# KR55_soundgen.net
KiCad netlist of a schematic drawn in EAGLE
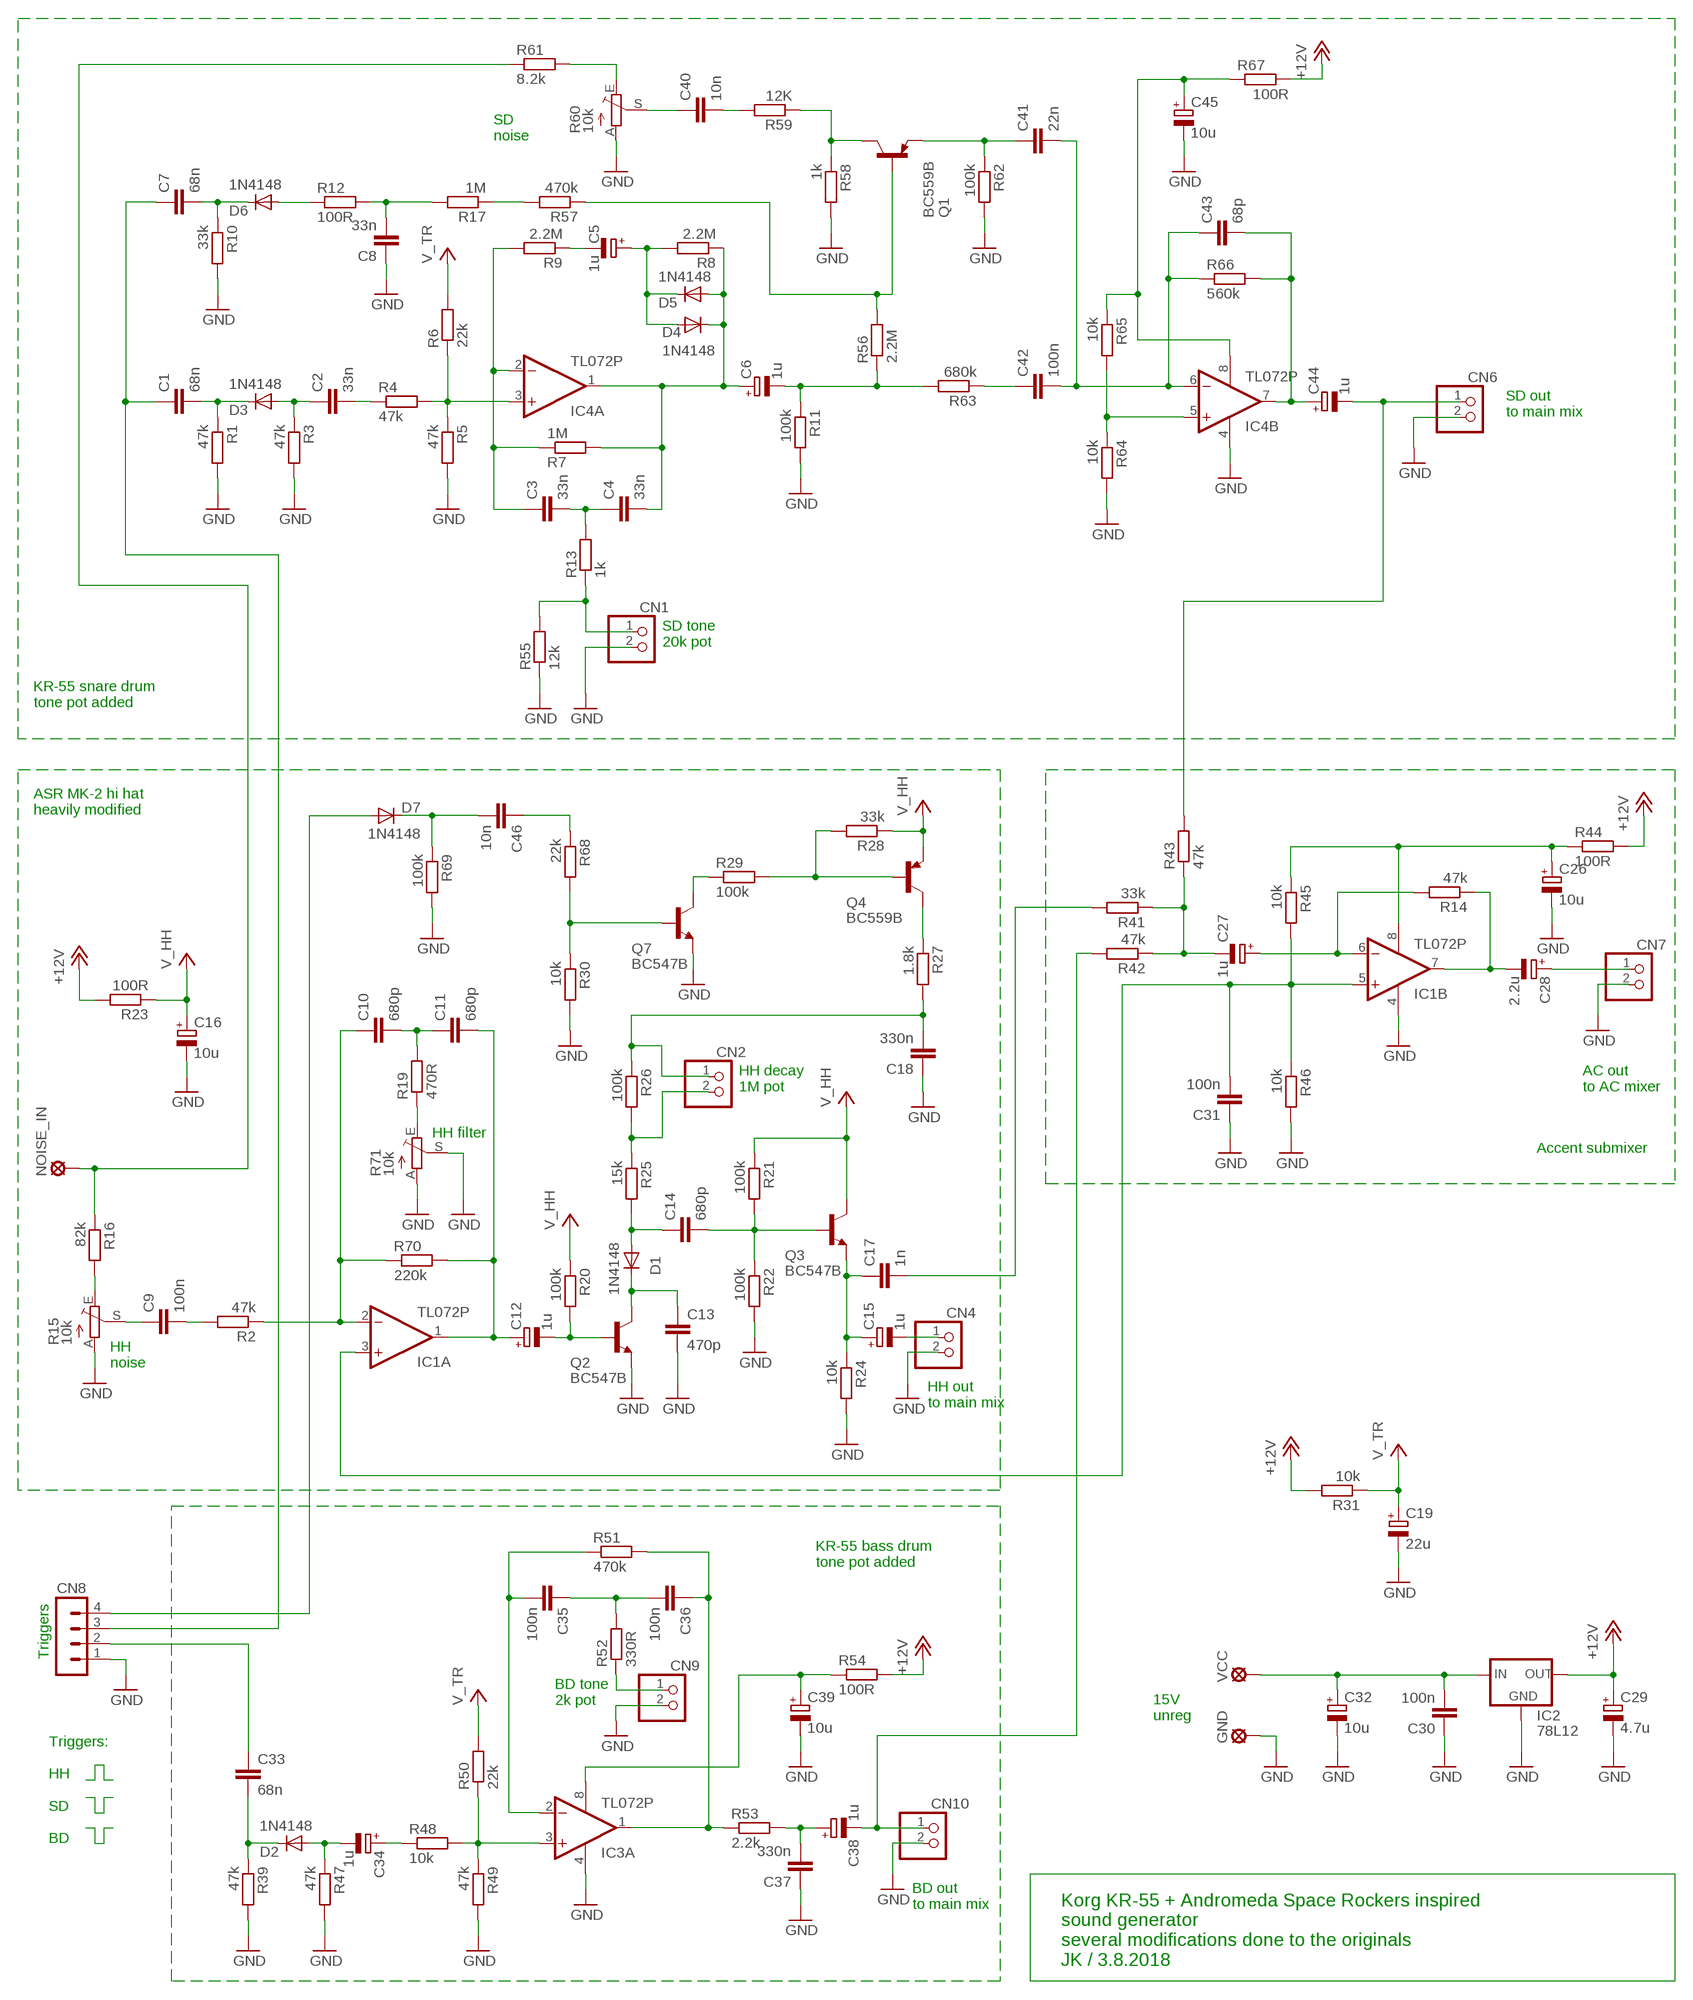
[diagram p0: schematic, sheet 1]

(export (version "E")
  (design (tool "Eeschema 10.0.6"))
  (components
    (comp (ref "C1")
      (value "68n")
      (footprint "eagle-import:C0805")
      (libsource (lib "eagle-import") (part "C-EUC0805"))
    )
    (comp (ref "C2")
      (value "33n")
      (footprint "eagle-import:C0805")
      (libsource (lib "eagle-import") (part "C-EUC0805"))
    )
    (comp (ref "C3")
      (value "33n")
      (footprint "eagle-import:C0805")
      (libsource (lib "eagle-import") (part "C-EUC0805"))
    )
    (comp (ref "C4")
      (value "33n")
      (footprint "eagle-import:C0805")
      (libsource (lib "eagle-import") (part "C-EUC0805"))
    )
    (comp (ref "C5")
      (value "1u")
      (footprint "eagle-import:SMC_A")
      (libsource (lib "eagle-import") (part "CPOL-EUSMCA"))
    )
    (comp (ref "C6")
      (value "1u")
      (footprint "eagle-import:SMC_A")
      (libsource (lib "eagle-import") (part "CPOL-EUSMCA"))
    )
    (comp (ref "C7")
      (value "68n")
      (footprint "eagle-import:C0805")
      (libsource (lib "eagle-import") (part "C-EUC0805"))
    )
    (comp (ref "C8")
      (value "33n")
      (footprint "eagle-import:C0805")
      (libsource (lib "eagle-import") (part "C-EUC0805"))
    )
    (comp (ref "C9")
      (value "100n")
      (footprint "eagle-import:C0805")
      (libsource (lib "eagle-import") (part "C-EUC0805"))
    )
    (comp (ref "C10")
      (value "680p")
      (footprint "eagle-import:C0805")
      (libsource (lib "eagle-import") (part "C-EUC0805"))
    )
    (comp (ref "C11")
      (value "680p")
      (footprint "eagle-import:C0805")
      (libsource (lib "eagle-import") (part "C-EUC0805"))
    )
    (comp (ref "C12")
      (value "1u")
      (footprint "eagle-import:SMC_A")
      (libsource (lib "eagle-import") (part "CPOL-EUSMCA"))
    )
    (comp (ref "C13")
      (value "470p")
      (footprint "eagle-import:C0805")
      (libsource (lib "eagle-import") (part "C-EUC0805"))
    )
    (comp (ref "C14")
      (value "680p")
      (footprint "eagle-import:C0805")
      (libsource (lib "eagle-import") (part "C-EUC0805"))
    )
    (comp (ref "C15")
      (value "1u")
      (footprint "eagle-import:SMC_A")
      (libsource (lib "eagle-import") (part "CPOL-EUSMCA"))
    )
    (comp (ref "C16")
      (value "10u")
      (footprint "eagle-import:E2,5-5")
      (libsource (lib "eagle-import") (part "CPOL-EUE2.5-5"))
    )
    (comp (ref "C17")
      (value "1n")
      (footprint "eagle-import:C0805")
      (libsource (lib "eagle-import") (part "C-EUC0805"))
    )
    (comp (ref "C18")
      (value "330n")
      (footprint "eagle-import:C0805")
      (libsource (lib "eagle-import") (part "C-EUC0805"))
    )
    (comp (ref "C19")
      (value "22u")
      (footprint "eagle-import:E2,5-5")
      (libsource (lib "eagle-import") (part "CPOL-EUE2.5-5"))
    )
    (comp (ref "C26")
      (value "10u")
      (footprint "eagle-import:E5-5")
      (libsource (lib "eagle-import") (part "CPOL-EUE5-5"))
    )
    (comp (ref "C27")
      (value "1u")
      (footprint "eagle-import:SMC_A")
      (libsource (lib "eagle-import") (part "CPOL-EUSMCA"))
    )
    (comp (ref "C28")
      (value "2.2u")
      (footprint "eagle-import:SMC_A")
      (libsource (lib "eagle-import") (part "CPOL-EUSMCA"))
    )
    (comp (ref "C29")
      (value "4.7u")
      (footprint "eagle-import:SMC_A")
      (libsource (lib "eagle-import") (part "CPOL-EUSMCA"))
    )
    (comp (ref "C30")
      (value "100n")
      (footprint "eagle-import:C0805")
      (libsource (lib "eagle-import") (part "C-EUC0805"))
    )
    (comp (ref "C31")
      (value "100n")
      (footprint "eagle-import:C0805")
      (libsource (lib "eagle-import") (part "C-EUC0805"))
    )
    (comp (ref "C32")
      (value "10u")
      (footprint "eagle-import:E2,5-5")
      (libsource (lib "eagle-import") (part "CPOL-EUE2.5-5"))
    )
    (comp (ref "C33")
      (value "68n")
      (footprint "eagle-import:C0805")
      (libsource (lib "eagle-import") (part "C-EUC0805"))
    )
    (comp (ref "C34")
      (value "1u")
      (footprint "eagle-import:SMC_A")
      (libsource (lib "eagle-import") (part "CPOL-EUSMCA"))
    )
    (comp (ref "C35")
      (value "100n")
      (footprint "eagle-import:C0805")
      (libsource (lib "eagle-import") (part "C-EUC0805"))
    )
    (comp (ref "C36")
      (value "100n")
      (footprint "eagle-import:C0805")
      (libsource (lib "eagle-import") (part "C-EUC0805"))
    )
    (comp (ref "C37")
      (value "330n")
      (footprint "eagle-import:C0805")
      (libsource (lib "eagle-import") (part "C-EUC0805"))
    )
    (comp (ref "C38")
      (value "1u")
      (footprint "eagle-import:SMC_A")
      (libsource (lib "eagle-import") (part "CPOL-EUSMCA"))
    )
    (comp (ref "C39")
      (value "10u")
      (footprint "eagle-import:E2,5-5")
      (libsource (lib "eagle-import") (part "CPOL-EUE2.5-5"))
    )
    (comp (ref "C40")
      (value "10n")
      (footprint "eagle-import:C1206")
      (libsource (lib "eagle-import") (part "C-EUC1206"))
    )
    (comp (ref "C41")
      (value "22n")
      (footprint "eagle-import:C0805")
      (libsource (lib "eagle-import") (part "C-EUC0805"))
    )
    (comp (ref "C42")
      (value "100n")
      (footprint "eagle-import:C050-024X044")
      (libsource (lib "eagle-import") (part "C-EU050-024X044"))
    )
    (comp (ref "C43")
      (value "68p")
      (footprint "eagle-import:C0805")
      (libsource (lib "eagle-import") (part "C-EUC0805"))
    )
    (comp (ref "C44")
      (value "1u")
      (footprint "eagle-import:SMC_A")
      (libsource (lib "eagle-import") (part "CPOL-EUSMCA"))
    )
    (comp (ref "C45")
      (value "10u")
      (footprint "eagle-import:E2,5-5")
      (libsource (lib "eagle-import") (part "CPOL-EUE2.5-5"))
    )
    (comp (ref "C46")
      (value "10n")
      (footprint "eagle-import:C0805")
      (libsource (lib "eagle-import") (part "C-EUC0805"))
    )
    (comp (ref "CN1")
      (value "PINHD-1X2")
      (footprint "eagle-import:1X02")
      (libsource (lib "eagle-import") (part "PINHD-1X2"))
    )
    (comp (ref "CN2")
      (value "PINHD-1X2")
      (footprint "eagle-import:1X02")
      (libsource (lib "eagle-import") (part "PINHD-1X2"))
    )
    (comp (ref "CN4")
      (value "PINHD-1X2")
      (footprint "eagle-import:1X02")
      (libsource (lib "eagle-import") (part "PINHD-1X2"))
    )
    (comp (ref "CN6")
      (value "PINHD-1X2")
      (footprint "eagle-import:1X02")
      (libsource (lib "eagle-import") (part "PINHD-1X2"))
    )
    (comp (ref "CN7")
      (value "PINHD-1X2")
      (footprint "eagle-import:1X02")
      (libsource (lib "eagle-import") (part "PINHD-1X2"))
    )
    (comp (ref "CN8")
      (value "MA04-1")
      (footprint "eagle-import:MA04-1")
      (libsource (lib "eagle-import") (part "MA04-1"))
    )
    (comp (ref "CN9")
      (value "PINHD-1X2")
      (footprint "eagle-import:1X02")
      (libsource (lib "eagle-import") (part "PINHD-1X2"))
    )
    (comp (ref "CN10")
      (value "PINHD-1X2")
      (footprint "eagle-import:1X02")
      (libsource (lib "eagle-import") (part "PINHD-1X2"))
    )
    (comp (ref "D1")
      (value "1N4148")
      (footprint "eagle-import:SOD80C")
      (libsource (lib "eagle-import") (part "DIODE-SOD80C"))
    )
    (comp (ref "D2")
      (value "1N4148")
      (footprint "eagle-import:SOD80C")
      (libsource (lib "eagle-import") (part "DIODE-SOD80C"))
    )
    (comp (ref "D3")
      (value "1N4148")
      (footprint "eagle-import:SOD80C")
      (libsource (lib "eagle-import") (part "DIODE-SOD80C"))
    )
    (comp (ref "D4")
      (value "1N4148")
      (footprint "eagle-import:SOD80C")
      (libsource (lib "eagle-import") (part "DIODE-SOD80C"))
    )
    (comp (ref "D5")
      (value "1N4148")
      (footprint "eagle-import:SOD80C")
      (libsource (lib "eagle-import") (part "DIODE-SOD80C"))
    )
    (comp (ref "D6")
      (value "1N4148")
      (footprint "eagle-import:SOD80C")
      (libsource (lib "eagle-import") (part "DIODE-SOD80C"))
    )
    (comp (ref "D7")
      (value "1N4148")
      (footprint "eagle-import:DO35-10")
      (libsource (lib "eagle-import") (part "DIODE-DO35-10"))
    )
    (comp (ref "GND")
      (value "LSP10")
      (footprint "eagle-import:LSP10")
      (libsource (lib "eagle-import") (part "LSP10"))
    )
    (comp (ref "IC1")
      (value "TL072P")
      (footprint "eagle-import:DIL08")
      (libsource (lib "eagle-import") (part "TL072P"))
    )
    (comp (ref "IC2")
      (value "78L12")
      (footprint "eagle-import:78LXX")
      (libsource (lib "eagle-import") (part "78LXX"))
    )
    (comp (ref "IC3")
      (value "TL072P")
      (footprint "eagle-import:DIL08")
      (libsource (lib "eagle-import") (part "TL072P"))
    )
    (comp (ref "IC4")
      (value "TL072P")
      (footprint "eagle-import:DIL08")
      (libsource (lib "eagle-import") (part "TL072P"))
    )
    (comp (ref "NOISE_IN")
      (value "LSP10")
      (footprint "eagle-import:LSP10")
      (libsource (lib "eagle-import") (part "LSP10"))
    )
    (comp (ref "Q1")
      (value "BC559B")
      (footprint "eagle-import:TO92-EBC")
      (libsource (lib "eagle-import") (part "BC559B"))
    )
    (comp (ref "Q2")
      (value "BC547B")
      (footprint "eagle-import:TO92")
      (libsource (lib "eagle-import") (part "BC547B"))
    )
    (comp (ref "Q3")
      (value "BC547B")
      (footprint "eagle-import:TO92")
      (libsource (lib "eagle-import") (part "BC547B"))
    )
    (comp (ref "Q4")
      (value "BC559B")
      (footprint "eagle-import:TO92-EBC")
      (libsource (lib "eagle-import") (part "BC559B"))
    )
    (comp (ref "Q7")
      (value "BC547B")
      (footprint "eagle-import:TO92")
      (libsource (lib "eagle-import") (part "BC547B"))
    )
    (comp (ref "R1")
      (value "47k")
      (footprint "eagle-import:R0805")
      (libsource (lib "eagle-import") (part "R-EU_R0805"))
    )
    (comp (ref "R2")
      (value "47k")
      (footprint "eagle-import:R0805")
      (libsource (lib "eagle-import") (part "R-EU_R0805"))
    )
    (comp (ref "R3")
      (value "47k")
      (footprint "eagle-import:R0805")
      (libsource (lib "eagle-import") (part "R-EU_R0805"))
    )
    (comp (ref "R4")
      (value "47k")
      (footprint "eagle-import:R0805")
      (libsource (lib "eagle-import") (part "R-EU_R0805"))
    )
    (comp (ref "R5")
      (value "47k")
      (footprint "eagle-import:R0805")
      (libsource (lib "eagle-import") (part "R-EU_R0805"))
    )
    (comp (ref "R6")
      (value "22k")
      (footprint "eagle-import:R0805")
      (libsource (lib "eagle-import") (part "R-EU_R0805"))
    )
    (comp (ref "R7")
      (value "1M")
      (footprint "eagle-import:R0805")
      (libsource (lib "eagle-import") (part "R-EU_R0805"))
    )
    (comp (ref "R8")
      (value "2.2M")
      (footprint "eagle-import:R0805")
      (libsource (lib "eagle-import") (part "R-EU_R0805"))
    )
    (comp (ref "R9")
      (value "2.2M")
      (footprint "eagle-import:R0805")
      (libsource (lib "eagle-import") (part "R-EU_R0805"))
    )
    (comp (ref "R10")
      (value "33k")
      (footprint "eagle-import:R0805")
      (libsource (lib "eagle-import") (part "R-EU_R0805"))
    )
    (comp (ref "R11")
      (value "100k")
      (footprint "eagle-import:R0805")
      (libsource (lib "eagle-import") (part "R-EU_R0805"))
    )
    (comp (ref "R12")
      (value "100R")
      (footprint "eagle-import:R0805")
      (libsource (lib "eagle-import") (part "R-EU_R0805"))
    )
    (comp (ref "R13")
      (value "1k")
      (footprint "eagle-import:R0805")
      (libsource (lib "eagle-import") (part "R-EU_R0805"))
    )
    (comp (ref "R14")
      (value "47k")
      (footprint "eagle-import:R0805")
      (libsource (lib "eagle-import") (part "R-EU_R0805"))
    )
    (comp (ref "R15")
      (value "10k")
      (footprint "eagle-import:S63X")
      (libsource (lib "eagle-import") (part "TRIM_EU-S63X"))
    )
    (comp (ref "R16")
      (value "82k")
      (footprint "eagle-import:R0805")
      (libsource (lib "eagle-import") (part "R-EU_R0805"))
    )
    (comp (ref "R17")
      (value "1M")
      (footprint "eagle-import:R0805")
      (libsource (lib "eagle-import") (part "R-EU_R0805"))
    )
    (comp (ref "R19")
      (value "470R")
      (footprint "eagle-import:0207_10")
      (libsource (lib "eagle-import") (part "R-EU_0207/10"))
    )
    (comp (ref "R20")
      (value "100k")
      (footprint "eagle-import:0207_10")
      (libsource (lib "eagle-import") (part "R-EU_0207/10"))
    )
    (comp (ref "R21")
      (value "100k")
      (footprint "eagle-import:R0805")
      (libsource (lib "eagle-import") (part "R-EU_R0805"))
    )
    (comp (ref "R22")
      (value "100k")
      (footprint "eagle-import:R0805")
      (libsource (lib "eagle-import") (part "R-EU_R0805"))
    )
    (comp (ref "R23")
      (value "100R")
      (footprint "eagle-import:R0805")
      (libsource (lib "eagle-import") (part "R-EU_R0805"))
    )
    (comp (ref "R24")
      (value "10k")
      (footprint "eagle-import:R0805")
      (libsource (lib "eagle-import") (part "R-EU_R0805"))
    )
    (comp (ref "R25")
      (value "15k")
      (footprint "eagle-import:0207_10")
      (libsource (lib "eagle-import") (part "R-EU_0207/10"))
    )
    (comp (ref "R26")
      (value "100k")
      (footprint "eagle-import:R0805")
      (libsource (lib "eagle-import") (part "R-EU_R0805"))
    )
    (comp (ref "R27")
      (value "1.8k")
      (footprint "eagle-import:0207_10")
      (libsource (lib "eagle-import") (part "R-EU_0207/10"))
    )
    (comp (ref "R28")
      (value "33k")
      (footprint "eagle-import:R0805")
      (libsource (lib "eagle-import") (part "R-EU_R0805"))
    )
    (comp (ref "R29")
      (value "100k")
      (footprint "eagle-import:R0805")
      (libsource (lib "eagle-import") (part "R-EU_R0805"))
    )
    (comp (ref "R30")
      (value "10k")
      (footprint "eagle-import:R0805")
      (libsource (lib "eagle-import") (part "R-EU_R0805"))
    )
    (comp (ref "R31")
      (value "10k")
      (footprint "eagle-import:R0805")
      (libsource (lib "eagle-import") (part "R-EU_R0805"))
    )
    (comp (ref "R39")
      (value "47k")
      (footprint "eagle-import:R0805")
      (libsource (lib "eagle-import") (part "R-EU_R0805"))
    )
    (comp (ref "R41")
      (value "33k")
      (footprint "eagle-import:R0805")
      (libsource (lib "eagle-import") (part "R-EU_R0805"))
    )
    (comp (ref "R42")
      (value "47k")
      (footprint "eagle-import:R0805")
      (libsource (lib "eagle-import") (part "R-EU_R0805"))
    )
    (comp (ref "R43")
      (value "47k")
      (footprint "eagle-import:R0805")
      (libsource (lib "eagle-import") (part "R-EU_R0805"))
    )
    (comp (ref "R44")
      (value "100R")
      (footprint "eagle-import:0207_10")
      (libsource (lib "eagle-import") (part "R-EU_0207/10"))
    )
    (comp (ref "R45")
      (value "10k")
      (footprint "eagle-import:R0805")
      (libsource (lib "eagle-import") (part "R-EU_R0805"))
    )
    (comp (ref "R46")
      (value "10k")
      (footprint "eagle-import:R0805")
      (libsource (lib "eagle-import") (part "R-EU_R0805"))
    )
    (comp (ref "R47")
      (value "47k")
      (footprint "eagle-import:R0805")
      (libsource (lib "eagle-import") (part "R-EU_R0805"))
    )
    (comp (ref "R48")
      (value "10k")
      (footprint "eagle-import:R0805")
      (libsource (lib "eagle-import") (part "R-EU_R0805"))
    )
    (comp (ref "R49")
      (value "47k")
      (footprint "eagle-import:R0805")
      (libsource (lib "eagle-import") (part "R-EU_R0805"))
    )
    (comp (ref "R50")
      (value "22k")
      (footprint "eagle-import:R0805")
      (libsource (lib "eagle-import") (part "R-EU_R0805"))
    )
    (comp (ref "R51")
      (value "470k")
      (footprint "eagle-import:R0805")
      (libsource (lib "eagle-import") (part "R-EU_R0805"))
    )
    (comp (ref "R52")
      (value "330R")
      (footprint "eagle-import:R0805")
      (libsource (lib "eagle-import") (part "R-EU_R0805"))
    )
    (comp (ref "R53")
      (value "2.2k")
      (footprint "eagle-import:0207_10")
      (libsource (lib "eagle-import") (part "R-EU_0207/10"))
    )
    (comp (ref "R54")
      (value "100R")
      (footprint "eagle-import:0207_10")
      (libsource (lib "eagle-import") (part "R-EU_0207/10"))
    )
    (comp (ref "R55")
      (value "12k")
      (footprint "eagle-import:R0805")
      (libsource (lib "eagle-import") (part "R-EU_R0805"))
    )
    (comp (ref "R56")
      (value "2.2M")
      (footprint "eagle-import:R0805")
      (libsource (lib "eagle-import") (part "R-EU_R0805"))
    )
    (comp (ref "R57")
      (value "470k")
      (footprint "eagle-import:R0805")
      (libsource (lib "eagle-import") (part "R-EU_R0805"))
    )
    (comp (ref "R58")
      (value "1k")
      (footprint "eagle-import:R0805")
      (libsource (lib "eagle-import") (part "R-EU_R0805"))
    )
    (comp (ref "R59")
      (value "12K")
      (footprint "eagle-import:R0805")
      (libsource (lib "eagle-import") (part "R-EU_R0805"))
    )
    (comp (ref "R60")
      (value "10k")
      (footprint "eagle-import:S63X")
      (libsource (lib "eagle-import") (part "TRIM_EU-S63X"))
    )
    (comp (ref "R61")
      (value "8.2k")
      (footprint "eagle-import:R0805")
      (libsource (lib "eagle-import") (part "R-EU_R0805"))
    )
    (comp (ref "R62")
      (value "100k")
      (footprint "eagle-import:R0805")
      (libsource (lib "eagle-import") (part "R-EU_R0805"))
    )
    (comp (ref "R63")
      (value "680k")
      (footprint "eagle-import:R0805")
      (libsource (lib "eagle-import") (part "R-EU_R0805"))
    )
    (comp (ref "R64")
      (value "10k")
      (footprint "eagle-import:R0805")
      (libsource (lib "eagle-import") (part "R-EU_R0805"))
    )
    (comp (ref "R65")
      (value "10k")
      (footprint "eagle-import:R0805")
      (libsource (lib "eagle-import") (part "R-EU_R0805"))
    )
    (comp (ref "R66")
      (value "560k")
      (footprint "eagle-import:R0805")
      (libsource (lib "eagle-import") (part "R-EU_R0805"))
    )
    (comp (ref "R67")
      (value "100R")
      (footprint "eagle-import:R0805")
      (libsource (lib "eagle-import") (part "R-EU_R0805"))
    )
    (comp (ref "R68")
      (value "22k")
      (footprint "eagle-import:R0805")
      (libsource (lib "eagle-import") (part "R-EU_R0805"))
    )
    (comp (ref "R69")
      (value "100k")
      (footprint "eagle-import:R0805")
      (libsource (lib "eagle-import") (part "R-EU_R0805"))
    )
    (comp (ref "R70")
      (value "220k")
      (footprint "eagle-import:R0805")
      (libsource (lib "eagle-import") (part "R-EU_R0805"))
    )
    (comp (ref "R71")
      (value "10k")
      (footprint "eagle-import:S63X")
      (libsource (lib "eagle-import") (part "TRIM_EU-S63X"))
    )
    (comp (ref "VCC")
      (value "LSP10")
      (footprint "eagle-import:LSP10")
      (libsource (lib "eagle-import") (part "LSP10"))
    )
  )
  (nets
    (net (code "1") (name "+12V") (class "Default")
      (node (ref "C29") (pin "+") (pinfunction "+_+") (pintype "passive"))
      (node (ref "IC2") (pin "OUT") (pinfunction "OUT_OUT") (pintype "passive"))
      (node (ref "R23") (pin "2") (pinfunction "2_2") (pintype "passive"))
      (node (ref "R31") (pin "2") (pinfunction "2_2") (pintype "passive"))
      (node (ref "R44") (pin "2") (pinfunction "2_2") (pintype "passive"))
      (node (ref "R54") (pin "2") (pinfunction "2_2") (pintype "passive"))
      (node (ref "R67") (pin "2") (pinfunction "2_2") (pintype "passive"))
    )
    (net (code "2") (name "GND") (class "Default")
      (node (ref "C13") (pin "2") (pinfunction "2_2") (pintype "passive"))
      (node (ref "C16") (pin "-") (pinfunction "-_-") (pintype "passive"))
      (node (ref "C18") (pin "1") (pinfunction "1_1") (pintype "passive"))
      (node (ref "C19") (pin "-") (pinfunction "-_-") (pintype "passive"))
      (node (ref "C26") (pin "-") (pinfunction "-_-") (pintype "passive"))
      (node (ref "C29") (pin "-") (pinfunction "-_-") (pintype "passive"))
      (node (ref "C30") (pin "1") (pinfunction "1_1") (pintype "passive"))
      (node (ref "C31") (pin "1") (pinfunction "1_1") (pintype "passive"))
      (node (ref "C32") (pin "-") (pinfunction "-_-") (pintype "passive"))
      (node (ref "C37") (pin "1") (pinfunction "1_1") (pintype "passive"))
      (node (ref "C39") (pin "-") (pinfunction "-_-") (pintype "passive"))
      (node (ref "C45") (pin "-") (pinfunction "-_-") (pintype "passive"))
      (node (ref "C8") (pin "1") (pinfunction "1_1") (pintype "passive"))
      (node (ref "CN1") (pin "2") (pinfunction "2_2") (pintype "passive"))
      (node (ref "CN10") (pin "2") (pinfunction "2_2") (pintype "passive"))
      (node (ref "CN4") (pin "2") (pinfunction "2_2") (pintype "passive"))
      (node (ref "CN6") (pin "2") (pinfunction "2_2") (pintype "passive"))
      (node (ref "CN7") (pin "2") (pinfunction "2_2") (pintype "passive"))
      (node (ref "CN8") (pin "1") (pinfunction "1_1") (pintype "passive"))
      (node (ref "CN9") (pin "2") (pinfunction "2_2") (pintype "passive"))
      (node (ref "GND") (pin "MP") (pinfunction "MP_MP") (pintype "passive"))
      (node (ref "IC1") (pin "4") (pinfunction "V-_4") (pintype "power_in"))
      (node (ref "IC2") (pin "GND") (pinfunction "GND_GND") (pintype "input"))
      (node (ref "IC3") (pin "4") (pinfunction "V-_4") (pintype "power_in"))
      (node (ref "IC4") (pin "4") (pinfunction "V-_4") (pintype "power_in"))
      (node (ref "Q2") (pin "1") (pinfunction "E_1") (pintype "passive"))
      (node (ref "Q7") (pin "1") (pinfunction "E_1") (pintype "passive"))
      (node (ref "R1") (pin "2") (pinfunction "2_2") (pintype "passive"))
      (node (ref "R10") (pin "2") (pinfunction "2_2") (pintype "passive"))
      (node (ref "R11") (pin "2") (pinfunction "2_2") (pintype "passive"))
      (node (ref "R15") (pin "A") (pinfunction "A_A") (pintype "passive"))
      (node (ref "R22") (pin "2") (pinfunction "2_2") (pintype "passive"))
      (node (ref "R24") (pin "2") (pinfunction "2_2") (pintype "passive"))
      (node (ref "R3") (pin "2") (pinfunction "2_2") (pintype "passive"))
      (node (ref "R30") (pin "2") (pinfunction "2_2") (pintype "passive"))
      (node (ref "R39") (pin "2") (pinfunction "2_2") (pintype "passive"))
      (node (ref "R46") (pin "2") (pinfunction "2_2") (pintype "passive"))
      (node (ref "R47") (pin "2") (pinfunction "2_2") (pintype "passive"))
      (node (ref "R49") (pin "2") (pinfunction "2_2") (pintype "passive"))
      (node (ref "R5") (pin "2") (pinfunction "2_2") (pintype "passive"))
      (node (ref "R55") (pin "1") (pinfunction "1_1") (pintype "passive"))
      (node (ref "R58") (pin "2") (pinfunction "2_2") (pintype "passive"))
      (node (ref "R60") (pin "A") (pinfunction "A_A") (pintype "passive"))
      (node (ref "R62") (pin "2") (pinfunction "2_2") (pintype "passive"))
      (node (ref "R64") (pin "2") (pinfunction "2_2") (pintype "passive"))
      (node (ref "R69") (pin "2") (pinfunction "2_2") (pintype "passive"))
      (node (ref "R71") (pin "A") (pinfunction "A_A") (pintype "passive"))
      (node (ref "R71") (pin "S") (pinfunction "S_S") (pintype "passive"))
    )
    (net (code "3") (name "Net-(C1-Pad1)") (class "Default")
      (node (ref "C1") (pin "1") (pinfunction "1_1") (pintype "passive"))
      (node (ref "C7") (pin "1") (pinfunction "1_1") (pintype "passive"))
      (node (ref "CN8") (pin "3") (pinfunction "3_3") (pintype "passive"))
    )
    (net (code "4") (name "Net-(C1-Pad2)") (class "Default")
      (node (ref "C1") (pin "2") (pinfunction "2_2") (pintype "passive"))
      (node (ref "D3") (pin "C") (pinfunction "C_C") (pintype "passive"))
      (node (ref "R1") (pin "1") (pinfunction "1_1") (pintype "passive"))
    )
    (net (code "5") (name "Net-(C2-Pad1)") (class "Default")
      (node (ref "C2") (pin "1") (pinfunction "1_1") (pintype "passive"))
      (node (ref "D3") (pin "A") (pinfunction "A_A") (pintype "passive"))
      (node (ref "R3") (pin "1") (pinfunction "1_1") (pintype "passive"))
    )
    (net (code "6") (name "Net-(C2-Pad2)") (class "Default")
      (node (ref "C2") (pin "2") (pinfunction "2_2") (pintype "passive"))
      (node (ref "R4") (pin "1") (pinfunction "1_1") (pintype "passive"))
    )
    (net (code "7") (name "Net-(C3-Pad2)") (class "Default")
      (node (ref "C3") (pin "2") (pinfunction "2_2") (pintype "passive"))
      (node (ref "C4") (pin "1") (pinfunction "1_1") (pintype "passive"))
      (node (ref "R13") (pin "2") (pinfunction "2_2") (pintype "passive"))
    )
    (net (code "8") (name "Net-(C5-Pad+)") (class "Default")
      (node (ref "C5") (pin "+") (pinfunction "+_+") (pintype "passive"))
      (node (ref "D4") (pin "A") (pinfunction "A_A") (pintype "passive"))
      (node (ref "D5") (pin "C") (pinfunction "C_C") (pintype "passive"))
      (node (ref "R8") (pin "2") (pinfunction "2_2") (pintype "passive"))
    )
    (net (code "9") (name "Net-(C5-Pad-)") (class "Default")
      (node (ref "C5") (pin "-") (pinfunction "-_-") (pintype "passive"))
      (node (ref "R9") (pin "1") (pinfunction "1_1") (pintype "passive"))
    )
    (net (code "10") (name "Net-(C6-Pad-)") (class "Default")
      (node (ref "C6") (pin "-") (pinfunction "-_-") (pintype "passive"))
      (node (ref "R11") (pin "1") (pinfunction "1_1") (pintype "passive"))
      (node (ref "R56") (pin "1") (pinfunction "1_1") (pintype "passive"))
      (node (ref "R63") (pin "2") (pinfunction "2_2") (pintype "passive"))
    )
    (net (code "11") (name "Net-(C7-Pad2)") (class "Default")
      (node (ref "C7") (pin "2") (pinfunction "2_2") (pintype "passive"))
      (node (ref "D6") (pin "C") (pinfunction "C_C") (pintype "passive"))
      (node (ref "R10") (pin "1") (pinfunction "1_1") (pintype "passive"))
    )
    (net (code "12") (name "Net-(C8-Pad2)") (class "Default")
      (node (ref "C8") (pin "2") (pinfunction "2_2") (pintype "passive"))
      (node (ref "R12") (pin "2") (pinfunction "2_2") (pintype "passive"))
      (node (ref "R17") (pin "2") (pinfunction "2_2") (pintype "passive"))
    )
    (net (code "13") (name "Net-(C9-Pad1)") (class "Default")
      (node (ref "C9") (pin "1") (pinfunction "1_1") (pintype "passive"))
      (node (ref "R15") (pin "S") (pinfunction "S_S") (pintype "passive"))
    )
    (net (code "14") (name "Net-(C9-Pad2)") (class "Default")
      (node (ref "C9") (pin "2") (pinfunction "2_2") (pintype "passive"))
      (node (ref "R2") (pin "2") (pinfunction "2_2") (pintype "passive"))
    )
    (net (code "15") (name "Net-(C10-Pad2)") (class "Default")
      (node (ref "C10") (pin "2") (pinfunction "2_2") (pintype "passive"))
      (node (ref "C11") (pin "1") (pinfunction "1_1") (pintype "passive"))
      (node (ref "R19") (pin "2") (pinfunction "2_2") (pintype "passive"))
    )
    (net (code "16") (name "Net-(C14-Pad1)") (class "Default")
      (node (ref "C14") (pin "1") (pinfunction "1_1") (pintype "passive"))
      (node (ref "D1") (pin "A") (pinfunction "A_A") (pintype "passive"))
      (node (ref "R25") (pin "2") (pinfunction "2_2") (pintype "passive"))
    )
    (net (code "17") (name "Net-(C15-Pad-)") (class "Default")
      (node (ref "C15") (pin "-") (pinfunction "-_-") (pintype "passive"))
      (node (ref "CN4") (pin "1") (pinfunction "1_1") (pintype "passive"))
    )
    (net (code "18") (name "Net-(C17-Pad2)") (class "Default")
      (node (ref "C17") (pin "2") (pinfunction "2_2") (pintype "passive"))
      (node (ref "R41") (pin "2") (pinfunction "2_2") (pintype "passive"))
    )
    (net (code "19") (name "Net-(C18-Pad2)") (class "Default")
      (node (ref "C18") (pin "2") (pinfunction "2_2") (pintype "passive"))
      (node (ref "CN2") (pin "1") (pinfunction "1_1") (pintype "passive"))
      (node (ref "R26") (pin "1") (pinfunction "1_1") (pintype "passive"))
      (node (ref "R27") (pin "2") (pinfunction "2_2") (pintype "passive"))
    )
    (net (code "20") (name "Net-(C27-Pad-)") (class "Default")
      (node (ref "C27") (pin "-") (pinfunction "-_-") (pintype "passive"))
      (node (ref "R41") (pin "1") (pinfunction "1_1") (pintype "passive"))
      (node (ref "R42") (pin "1") (pinfunction "1_1") (pintype "passive"))
      (node (ref "R43") (pin "1") (pinfunction "1_1") (pintype "passive"))
    )
    (net (code "21") (name "Net-(C28-Pad+)") (class "Default")
      (node (ref "C28") (pin "+") (pinfunction "+_+") (pintype "passive"))
      (node (ref "CN7") (pin "1") (pinfunction "1_1") (pintype "passive"))
    )
    (net (code "22") (name "Net-(C30-Pad2)") (class "Default")
      (node (ref "C30") (pin "2") (pinfunction "2_2") (pintype "passive"))
      (node (ref "C32") (pin "+") (pinfunction "+_+") (pintype "passive"))
      (node (ref "IC2") (pin "IN") (pinfunction "IN_IN") (pintype "input"))
      (node (ref "VCC") (pin "MP") (pinfunction "MP_MP") (pintype "passive"))
    )
    (net (code "23") (name "Net-(C33-Pad1)") (class "Default")
      (node (ref "C33") (pin "1") (pinfunction "1_1") (pintype "passive"))
      (node (ref "CN8") (pin "2") (pinfunction "2_2") (pintype "passive"))
    )
    (net (code "24") (name "Net-(C33-Pad2)") (class "Default")
      (node (ref "C33") (pin "2") (pinfunction "2_2") (pintype "passive"))
      (node (ref "D2") (pin "C") (pinfunction "C_C") (pintype "passive"))
      (node (ref "R39") (pin "1") (pinfunction "1_1") (pintype "passive"))
    )
    (net (code "25") (name "Net-(C34-Pad+)") (class "Default")
      (node (ref "C34") (pin "+") (pinfunction "+_+") (pintype "passive"))
      (node (ref "R48") (pin "1") (pinfunction "1_1") (pintype "passive"))
    )
    (net (code "26") (name "Net-(C34-Pad-)") (class "Default")
      (node (ref "C34") (pin "-") (pinfunction "-_-") (pintype "passive"))
      (node (ref "D2") (pin "A") (pinfunction "A_A") (pintype "passive"))
      (node (ref "R47") (pin "1") (pinfunction "1_1") (pintype "passive"))
    )
    (net (code "27") (name "Net-(C35-Pad1)") (class "Default")
      (node (ref "C35") (pin "1") (pinfunction "1_1") (pintype "passive"))
      (node (ref "C36") (pin "2") (pinfunction "2_2") (pintype "passive"))
      (node (ref "R52") (pin "2") (pinfunction "2_2") (pintype "passive"))
    )
    (net (code "28") (name "Net-(C37-Pad2)") (class "Default")
      (node (ref "C37") (pin "2") (pinfunction "2_2") (pintype "passive"))
      (node (ref "C38") (pin "+") (pinfunction "+_+") (pintype "passive"))
      (node (ref "R53") (pin "2") (pinfunction "2_2") (pintype "passive"))
    )
    (net (code "29") (name "Net-(C38-Pad-)") (class "Default")
      (node (ref "C38") (pin "-") (pinfunction "-_-") (pintype "passive"))
      (node (ref "CN10") (pin "1") (pinfunction "1_1") (pintype "passive"))
      (node (ref "R42") (pin "2") (pinfunction "2_2") (pintype "passive"))
    )
    (net (code "30") (name "Net-(C40-Pad1)") (class "Default")
      (node (ref "C40") (pin "1") (pinfunction "1_1") (pintype "passive"))
      (node (ref "R60") (pin "S") (pinfunction "S_S") (pintype "passive"))
    )
    (net (code "31") (name "Net-(C40-Pad2)") (class "Default")
      (node (ref "C40") (pin "2") (pinfunction "2_2") (pintype "passive"))
      (node (ref "R59") (pin "2") (pinfunction "2_2") (pintype "passive"))
    )
    (net (code "32") (name "Net-(C41-Pad1)") (class "Default")
      (node (ref "C41") (pin "1") (pinfunction "1_1") (pintype "passive"))
      (node (ref "Q1") (pin "E") (pinfunction "E_E") (pintype "passive"))
      (node (ref "R62") (pin "1") (pinfunction "1_1") (pintype "passive"))
    )
    (net (code "33") (name "Net-(C42-Pad1)") (class "Default")
      (node (ref "C42") (pin "1") (pinfunction "1_1") (pintype "passive"))
      (node (ref "R63") (pin "1") (pinfunction "1_1") (pintype "passive"))
    )
    (net (code "34") (name "Net-(C44-Pad-)") (class "Default")
      (node (ref "C44") (pin "-") (pinfunction "-_-") (pintype "passive"))
      (node (ref "CN6") (pin "1") (pinfunction "1_1") (pintype "passive"))
      (node (ref "R43") (pin "2") (pinfunction "2_2") (pintype "passive"))
    )
    (net (code "35") (name "Net-(C46-Pad1)") (class "Default")
      (node (ref "C46") (pin "1") (pinfunction "1_1") (pintype "passive"))
      (node (ref "R68") (pin "1") (pinfunction "1_1") (pintype "passive"))
    )
    (net (code "36") (name "Net-(C46-Pad2)") (class "Default")
      (node (ref "C46") (pin "2") (pinfunction "2_2") (pintype "passive"))
      (node (ref "D7") (pin "C") (pinfunction "C_C") (pintype "passive"))
      (node (ref "R69") (pin "1") (pinfunction "1_1") (pintype "passive"))
    )
    (net (code "37") (name "Net-(CN1-Pad1)") (class "Default")
      (node (ref "CN1") (pin "1") (pinfunction "1_1") (pintype "passive"))
      (node (ref "R13") (pin "1") (pinfunction "1_1") (pintype "passive"))
      (node (ref "R55") (pin "2") (pinfunction "2_2") (pintype "passive"))
    )
    (net (code "38") (name "Net-(CN2-Pad2)") (class "Default")
      (node (ref "CN2") (pin "2") (pinfunction "2_2") (pintype "passive"))
      (node (ref "R25") (pin "1") (pinfunction "1_1") (pintype "passive"))
      (node (ref "R26") (pin "2") (pinfunction "2_2") (pintype "passive"))
    )
    (net (code "39") (name "Net-(CN8-Pad4)") (class "Default")
      (node (ref "CN8") (pin "4") (pinfunction "4_4") (pintype "passive"))
      (node (ref "D7") (pin "A") (pinfunction "A_A") (pintype "passive"))
    )
    (net (code "40") (name "Net-(CN9-Pad1)") (class "Default")
      (node (ref "CN9") (pin "1") (pinfunction "1_1") (pintype "passive"))
      (node (ref "R52") (pin "1") (pinfunction "1_1") (pintype "passive"))
    )
    (net (code "41") (name "Net-(D6-PadA)") (class "Default")
      (node (ref "D6") (pin "A") (pinfunction "A_A") (pintype "passive"))
      (node (ref "R12") (pin "1") (pinfunction "1_1") (pintype "passive"))
    )
    (net (code "42") (name "Net-(IC1A-+IN)") (class "Default")
      (node (ref "C31") (pin "2") (pinfunction "2_2") (pintype "passive"))
      (node (ref "IC1") (pin "3") (pinfunction "+IN_3") (pintype "input"))
      (node (ref "IC1") (pin "5") (pinfunction "+IN_5") (pintype "input"))
      (node (ref "R45") (pin "2") (pinfunction "2_2") (pintype "passive"))
      (node (ref "R46") (pin "1") (pinfunction "1_1") (pintype "passive"))
    )
    (net (code "43") (name "Net-(IC1A--IN)") (class "Default")
      (node (ref "C10") (pin "1") (pinfunction "1_1") (pintype "passive"))
      (node (ref "IC1") (pin "2") (pinfunction "-IN_2") (pintype "input"))
      (node (ref "R2") (pin "1") (pinfunction "1_1") (pintype "passive"))
      (node (ref "R70") (pin "1") (pinfunction "1_1") (pintype "passive"))
    )
    (net (code "44") (name "Net-(IC1A-OUT)") (class "Default")
      (node (ref "C11") (pin "2") (pinfunction "2_2") (pintype "passive"))
      (node (ref "C12") (pin "+") (pinfunction "+_+") (pintype "passive"))
      (node (ref "IC1") (pin "1") (pinfunction "OUT_1") (pintype "output"))
      (node (ref "R70") (pin "2") (pinfunction "2_2") (pintype "passive"))
    )
    (net (code "45") (name "Net-(IC1B--IN)") (class "Default")
      (node (ref "C27") (pin "+") (pinfunction "+_+") (pintype "passive"))
      (node (ref "IC1") (pin "6") (pinfunction "-IN_6") (pintype "input"))
      (node (ref "R14") (pin "2") (pinfunction "2_2") (pintype "passive"))
    )
    (net (code "46") (name "Net-(IC1B-OUT)") (class "Default")
      (node (ref "C28") (pin "-") (pinfunction "-_-") (pintype "passive"))
      (node (ref "IC1") (pin "7") (pinfunction "OUT_7") (pintype "output"))
      (node (ref "R14") (pin "1") (pinfunction "1_1") (pintype "passive"))
    )
    (net (code "47") (name "Net-(IC1C-V+)") (class "Default")
      (node (ref "C26") (pin "+") (pinfunction "+_+") (pintype "passive"))
      (node (ref "IC1") (pin "8") (pinfunction "V+_8") (pintype "power_in"))
      (node (ref "R44") (pin "1") (pinfunction "1_1") (pintype "passive"))
      (node (ref "R45") (pin "1") (pinfunction "1_1") (pintype "passive"))
    )
    (net (code "48") (name "Net-(IC3A-+IN)") (class "Default")
      (node (ref "IC3") (pin "3") (pinfunction "+IN_3") (pintype "input"))
      (node (ref "R48") (pin "2") (pinfunction "2_2") (pintype "passive"))
      (node (ref "R49") (pin "1") (pinfunction "1_1") (pintype "passive"))
      (node (ref "R50") (pin "1") (pinfunction "1_1") (pintype "passive"))
    )
    (net (code "49") (name "Net-(IC3A--IN)") (class "Default")
      (node (ref "C35") (pin "2") (pinfunction "2_2") (pintype "passive"))
      (node (ref "IC3") (pin "2") (pinfunction "-IN_2") (pintype "input"))
      (node (ref "R51") (pin "1") (pinfunction "1_1") (pintype "passive"))
    )
    (net (code "50") (name "Net-(IC3A-OUT)") (class "Default")
      (node (ref "C36") (pin "1") (pinfunction "1_1") (pintype "passive"))
      (node (ref "IC3") (pin "1") (pinfunction "OUT_1") (pintype "output"))
      (node (ref "R51") (pin "2") (pinfunction "2_2") (pintype "passive"))
      (node (ref "R53") (pin "1") (pinfunction "1_1") (pintype "passive"))
    )
    (net (code "51") (name "Net-(IC3C-V+)") (class "Default")
      (node (ref "C39") (pin "+") (pinfunction "+_+") (pintype "passive"))
      (node (ref "IC3") (pin "8") (pinfunction "V+_8") (pintype "power_in"))
      (node (ref "R54") (pin "1") (pinfunction "1_1") (pintype "passive"))
    )
    (net (code "52") (name "Net-(IC4A-+IN)") (class "Default")
      (node (ref "IC4") (pin "3") (pinfunction "+IN_3") (pintype "input"))
      (node (ref "R4") (pin "2") (pinfunction "2_2") (pintype "passive"))
      (node (ref "R5") (pin "1") (pinfunction "1_1") (pintype "passive"))
      (node (ref "R6") (pin "1") (pinfunction "1_1") (pintype "passive"))
    )
    (net (code "53") (name "Net-(IC4A--IN)") (class "Default")
      (node (ref "C3") (pin "1") (pinfunction "1_1") (pintype "passive"))
      (node (ref "IC4") (pin "2") (pinfunction "-IN_2") (pintype "input"))
      (node (ref "R7") (pin "1") (pinfunction "1_1") (pintype "passive"))
      (node (ref "R9") (pin "2") (pinfunction "2_2") (pintype "passive"))
    )
    (net (code "54") (name "Net-(IC4A-OUT)") (class "Default")
      (node (ref "C4") (pin "2") (pinfunction "2_2") (pintype "passive"))
      (node (ref "C6") (pin "+") (pinfunction "+_+") (pintype "passive"))
      (node (ref "D4") (pin "C") (pinfunction "C_C") (pintype "passive"))
      (node (ref "D5") (pin "A") (pinfunction "A_A") (pintype "passive"))
      (node (ref "IC4") (pin "1") (pinfunction "OUT_1") (pintype "output"))
      (node (ref "R7") (pin "2") (pinfunction "2_2") (pintype "passive"))
      (node (ref "R8") (pin "1") (pinfunction "1_1") (pintype "passive"))
    )
    (net (code "55") (name "Net-(IC4B-+IN)") (class "Default")
      (node (ref "IC4") (pin "5") (pinfunction "+IN_5") (pintype "input"))
      (node (ref "R64") (pin "1") (pinfunction "1_1") (pintype "passive"))
      (node (ref "R65") (pin "2") (pinfunction "2_2") (pintype "passive"))
    )
    (net (code "56") (name "Net-(IC4B--IN)") (class "Default")
      (node (ref "C41") (pin "2") (pinfunction "2_2") (pintype "passive"))
      (node (ref "C42") (pin "2") (pinfunction "2_2") (pintype "passive"))
      (node (ref "C43") (pin "1") (pinfunction "1_1") (pintype "passive"))
      (node (ref "IC4") (pin "6") (pinfunction "-IN_6") (pintype "input"))
      (node (ref "R66") (pin "1") (pinfunction "1_1") (pintype "passive"))
    )
    (net (code "57") (name "Net-(IC4B-OUT)") (class "Default")
      (node (ref "C43") (pin "2") (pinfunction "2_2") (pintype "passive"))
      (node (ref "C44") (pin "+") (pinfunction "+_+") (pintype "passive"))
      (node (ref "IC4") (pin "7") (pinfunction "OUT_7") (pintype "output"))
      (node (ref "R66") (pin "2") (pinfunction "2_2") (pintype "passive"))
    )
    (net (code "58") (name "Net-(IC4C-V+)") (class "Default")
      (node (ref "C45") (pin "+") (pinfunction "+_+") (pintype "passive"))
      (node (ref "IC4") (pin "8") (pinfunction "V+_8") (pintype "power_in"))
      (node (ref "R65") (pin "1") (pinfunction "1_1") (pintype "passive"))
      (node (ref "R67") (pin "1") (pinfunction "1_1") (pintype "passive"))
    )
    (net (code "59") (name "Net-(NOISE_IN-PadMP)") (class "Default")
      (node (ref "NOISE_IN") (pin "MP") (pinfunction "MP_MP") (pintype "passive"))
      (node (ref "R16") (pin "1") (pinfunction "1_1") (pintype "passive"))
      (node (ref "R61") (pin "1") (pinfunction "1_1") (pintype "passive"))
    )
    (net (code "60") (name "Net-(Q1-PadB)") (class "Default")
      (node (ref "Q1") (pin "B") (pinfunction "B_B") (pintype "passive"))
      (node (ref "R56") (pin "2") (pinfunction "2_2") (pintype "passive"))
      (node (ref "R57") (pin "1") (pinfunction "1_1") (pintype "passive"))
    )
    (net (code "61") (name "Net-(Q1-PadC)") (class "Default")
      (node (ref "Q1") (pin "C") (pinfunction "C_C") (pintype "passive"))
      (node (ref "R58") (pin "1") (pinfunction "1_1") (pintype "passive"))
      (node (ref "R59") (pin "1") (pinfunction "1_1") (pintype "passive"))
    )
    (net (code "62") (name "Net-(Q2-B)") (class "Default")
      (node (ref "C12") (pin "-") (pinfunction "-_-") (pintype "passive"))
      (node (ref "Q2") (pin "2") (pinfunction "B_2") (pintype "passive"))
      (node (ref "R20") (pin "2") (pinfunction "2_2") (pintype "passive"))
    )
    (net (code "63") (name "Net-(Q2-C)") (class "Default")
      (node (ref "C13") (pin "1") (pinfunction "1_1") (pintype "passive"))
      (node (ref "D1") (pin "C") (pinfunction "C_C") (pintype "passive"))
      (node (ref "Q2") (pin "3") (pinfunction "C_3") (pintype "passive"))
    )
    (net (code "64") (name "Net-(Q3-B)") (class "Default")
      (node (ref "C14") (pin "2") (pinfunction "2_2") (pintype "passive"))
      (node (ref "Q3") (pin "2") (pinfunction "B_2") (pintype "passive"))
      (node (ref "R21") (pin "2") (pinfunction "2_2") (pintype "passive"))
      (node (ref "R22") (pin "1") (pinfunction "1_1") (pintype "passive"))
    )
    (net (code "65") (name "Net-(Q3-E)") (class "Default")
      (node (ref "C15") (pin "+") (pinfunction "+_+") (pintype "passive"))
      (node (ref "C17") (pin "1") (pinfunction "1_1") (pintype "passive"))
      (node (ref "Q3") (pin "1") (pinfunction "E_1") (pintype "passive"))
      (node (ref "R24") (pin "1") (pinfunction "1_1") (pintype "passive"))
    )
    (net (code "66") (name "Net-(Q4-PadB)") (class "Default")
      (node (ref "Q4") (pin "B") (pinfunction "B_B") (pintype "passive"))
      (node (ref "R28") (pin "2") (pinfunction "2_2") (pintype "passive"))
      (node (ref "R29") (pin "2") (pinfunction "2_2") (pintype "passive"))
    )
    (net (code "67") (name "Net-(Q4-PadC)") (class "Default")
      (node (ref "Q4") (pin "C") (pinfunction "C_C") (pintype "passive"))
      (node (ref "R27") (pin "1") (pinfunction "1_1") (pintype "passive"))
    )
    (net (code "68") (name "Net-(Q7-B)") (class "Default")
      (node (ref "Q7") (pin "2") (pinfunction "B_2") (pintype "passive"))
      (node (ref "R30") (pin "1") (pinfunction "1_1") (pintype "passive"))
      (node (ref "R68") (pin "2") (pinfunction "2_2") (pintype "passive"))
    )
    (net (code "69") (name "Net-(Q7-C)") (class "Default")
      (node (ref "Q7") (pin "3") (pinfunction "C_3") (pintype "passive"))
      (node (ref "R29") (pin "1") (pinfunction "1_1") (pintype "passive"))
    )
    (net (code "70") (name "Net-(R15-PadE)") (class "Default")
      (node (ref "R15") (pin "E") (pinfunction "E_E") (pintype "passive"))
      (node (ref "R16") (pin "2") (pinfunction "2_2") (pintype "passive"))
    )
    (net (code "71") (name "Net-(R17-Pad1)") (class "Default")
      (node (ref "R17") (pin "1") (pinfunction "1_1") (pintype "passive"))
      (node (ref "R57") (pin "2") (pinfunction "2_2") (pintype "passive"))
    )
    (net (code "72") (name "Net-(R19-Pad1)") (class "Default")
      (node (ref "R19") (pin "1") (pinfunction "1_1") (pintype "passive"))
      (node (ref "R71") (pin "E") (pinfunction "E_E") (pintype "passive"))
    )
    (net (code "73") (name "Net-(R60-PadE)") (class "Default")
      (node (ref "R60") (pin "E") (pinfunction "E_E") (pintype "passive"))
      (node (ref "R61") (pin "2") (pinfunction "2_2") (pintype "passive"))
    )
    (net (code "74") (name "V_HH") (class "Default")
      (node (ref "C16") (pin "+") (pinfunction "+_+") (pintype "passive"))
      (node (ref "Q3") (pin "3") (pinfunction "C_3") (pintype "passive"))
      (node (ref "Q4") (pin "E") (pinfunction "E_E") (pintype "passive"))
      (node (ref "R20") (pin "1") (pinfunction "1_1") (pintype "passive"))
      (node (ref "R21") (pin "1") (pinfunction "1_1") (pintype "passive"))
      (node (ref "R23") (pin "1") (pinfunction "1_1") (pintype "passive"))
      (node (ref "R28") (pin "1") (pinfunction "1_1") (pintype "passive"))
    )
    (net (code "75") (name "V_TR") (class "Default")
      (node (ref "C19") (pin "+") (pinfunction "+_+") (pintype "passive"))
      (node (ref "R31") (pin "1") (pinfunction "1_1") (pintype "passive"))
      (node (ref "R50") (pin "2") (pinfunction "2_2") (pintype "passive"))
      (node (ref "R6") (pin "2") (pinfunction "2_2") (pintype "passive"))
    )
  )
)
